# RobotCtrl_Func.net
KiCad netlist of a schematic drawn in Altium Designer
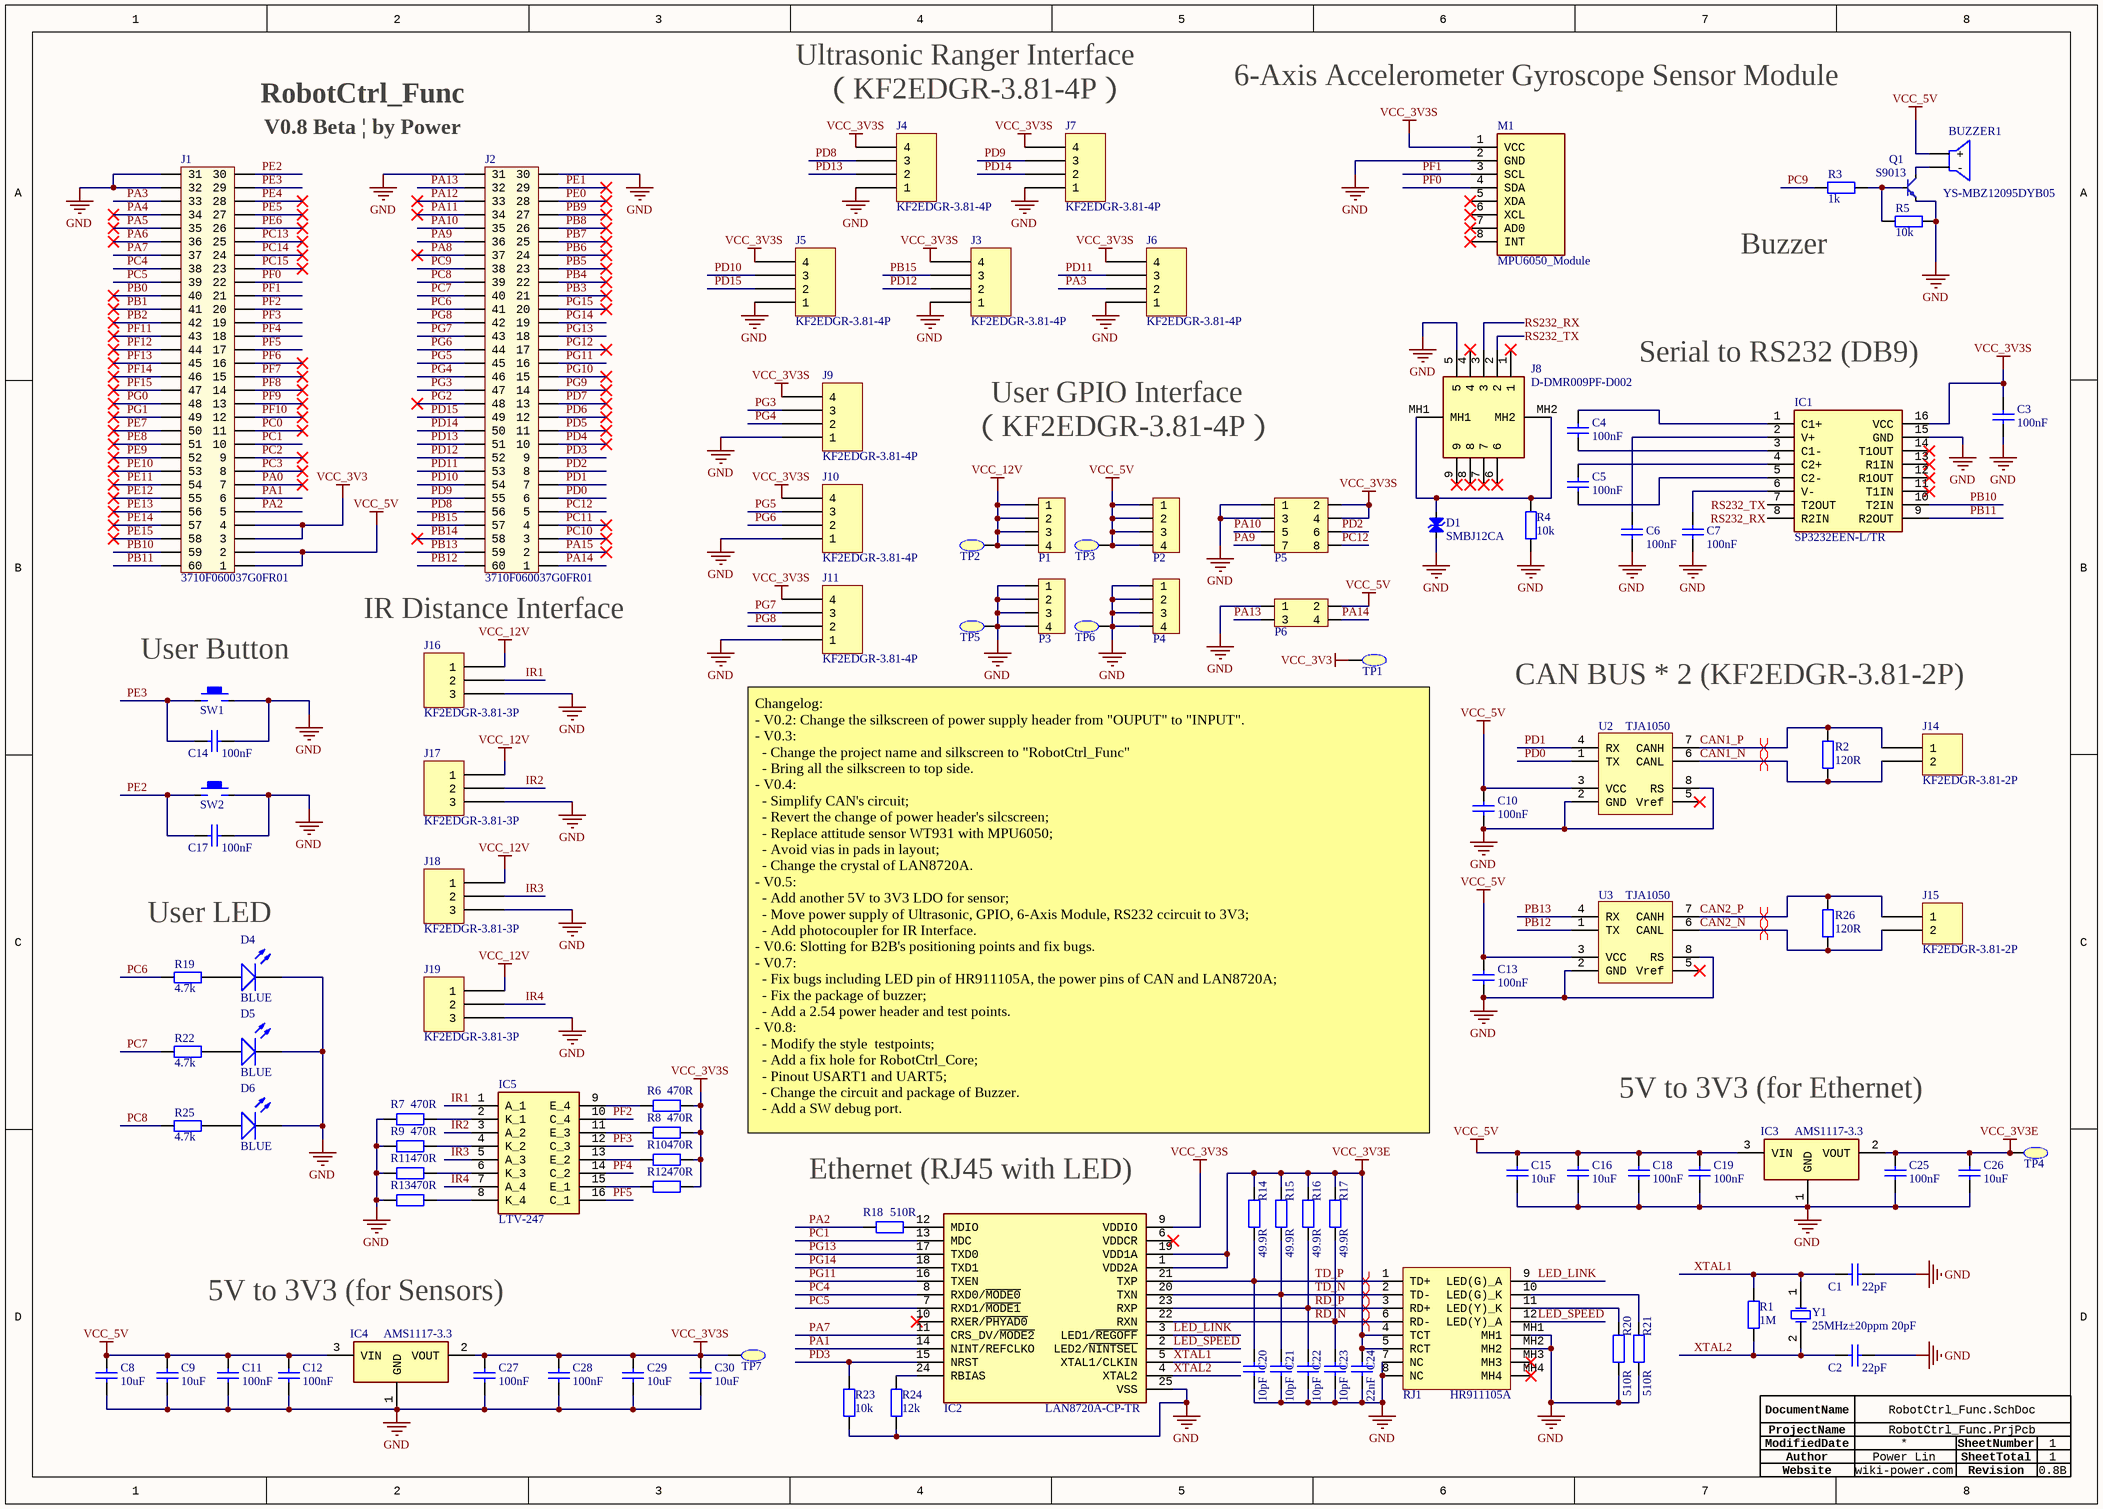
[diagram p0: RobotCtrl_Func.SchDoc]

(export (version "E")
  (design (tool "Eeschema 10.0.6"))
  (components
    (comp (ref "BUZZER1")
      (value "YS-MBZ12095DYB05")
      (footprint "DIP,P=7.6mm")
      (description "YS-MBZ12095DYB05 有源蜂鸣器")
      (libsource (lib "Power_Lib_Altium") (part "BUZZER"))
    )
    (comp (ref "C1")
      (value "22pF")
      (footprint "CAP-0603")
      (description "贴片电容")
      (libsource (lib "Power_Lib_Altium") (part "CAP"))
    )
    (comp (ref "C2")
      (value "22pF")
      (footprint "CAP-0603")
      (description "贴片电容")
      (libsource (lib "Power_Lib_Altium") (part "CAP"))
    )
    (comp (ref "C3")
      (value "100nF")
      (footprint "CAP-0603")
      (description "贴片电容")
      (libsource (lib "Power_Lib_Altium") (part "CAP"))
    )
    (comp (ref "C4")
      (value "100nF")
      (footprint "CAP-0603")
      (description "贴片电容")
      (libsource (lib "Power_Lib_Altium") (part "CAP"))
    )
    (comp (ref "C5")
      (value "100nF")
      (footprint "CAP-0603")
      (description "贴片电容")
      (libsource (lib "Power_Lib_Altium") (part "CAP"))
    )
    (comp (ref "C6")
      (value "100nF")
      (footprint "CAP-0603")
      (description "贴片电容")
      (libsource (lib "Power_Lib_Altium") (part "CAP"))
    )
    (comp (ref "C7")
      (value "100nF")
      (footprint "CAP-0603")
      (description "贴片电容")
      (libsource (lib "Power_Lib_Altium") (part "CAP"))
    )
    (comp (ref "C8")
      (value "10uF")
      (footprint "CAP-0603")
      (description "贴片电容")
      (libsource (lib "Power_Lib_Altium") (part "CAP"))
    )
    (comp (ref "C9")
      (value "10uF")
      (footprint "CAP-0603")
      (description "贴片电容")
      (libsource (lib "Power_Lib_Altium") (part "CAP"))
    )
    (comp (ref "C10")
      (value "100nF")
      (footprint "CAP-0603")
      (description "贴片电容")
      (libsource (lib "Power_Lib_Altium") (part "CAP"))
    )
    (comp (ref "C11")
      (value "100nF")
      (footprint "CAP-0603")
      (description "贴片电容")
      (libsource (lib "Power_Lib_Altium") (part "CAP"))
    )
    (comp (ref "C12")
      (value "100nF")
      (footprint "CAP-0603")
      (description "贴片电容")
      (libsource (lib "Power_Lib_Altium") (part "CAP"))
    )
    (comp (ref "C13")
      (value "100nF")
      (footprint "CAP-0603")
      (description "贴片电容")
      (libsource (lib "Power_Lib_Altium") (part "CAP"))
    )
    (comp (ref "C14")
      (value "100nF")
      (footprint "CAP-0603")
      (description "贴片电容")
      (libsource (lib "Power_Lib_Altium") (part "CAP"))
    )
    (comp (ref "C15")
      (value "10uF")
      (footprint "CAP-0603")
      (description "贴片电容")
      (libsource (lib "Power_Lib_Altium") (part "CAP"))
    )
    (comp (ref "C16")
      (value "10uF")
      (footprint "CAP-0603")
      (description "贴片电容")
      (libsource (lib "Power_Lib_Altium") (part "CAP"))
    )
    (comp (ref "C17")
      (value "100nF")
      (footprint "CAP-0603")
      (description "贴片电容")
      (libsource (lib "Power_Lib_Altium") (part "CAP"))
    )
    (comp (ref "C18")
      (value "100nF")
      (footprint "CAP-0603")
      (description "贴片电容")
      (libsource (lib "Power_Lib_Altium") (part "CAP"))
    )
    (comp (ref "C19")
      (value "100nF")
      (footprint "CAP-0603")
      (description "贴片电容")
      (libsource (lib "Power_Lib_Altium") (part "CAP"))
    )
    (comp (ref "C20")
      (value "10pF")
      (footprint "CAP-0603")
      (description "贴片电容")
      (libsource (lib "Power_Lib_Altium") (part "CAP"))
    )
    (comp (ref "C21")
      (value "10pF")
      (footprint "CAP-0603")
      (description "贴片电容")
      (libsource (lib "Power_Lib_Altium") (part "CAP"))
    )
    (comp (ref "C22")
      (value "10pF")
      (footprint "CAP-0603")
      (description "贴片电容")
      (libsource (lib "Power_Lib_Altium") (part "CAP"))
    )
    (comp (ref "C23")
      (value "10pF")
      (footprint "CAP-0603")
      (description "贴片电容")
      (libsource (lib "Power_Lib_Altium") (part "CAP"))
    )
    (comp (ref "C24")
      (value "22nF")
      (footprint "CAP-0603")
      (description "贴片电容")
      (libsource (lib "Power_Lib_Altium") (part "CAP"))
    )
    (comp (ref "C25")
      (value "100nF")
      (footprint "CAP-0603")
      (description "贴片电容")
      (libsource (lib "Power_Lib_Altium") (part "CAP"))
    )
    (comp (ref "C26")
      (value "10uF")
      (footprint "CAP-0603")
      (description "贴片电容")
      (libsource (lib "Power_Lib_Altium") (part "CAP"))
    )
    (comp (ref "C27")
      (value "100nF")
      (footprint "CAP-0603")
      (description "贴片电容")
      (libsource (lib "Power_Lib_Altium") (part "CAP"))
    )
    (comp (ref "C28")
      (value "100nF")
      (footprint "CAP-0603")
      (description "贴片电容")
      (libsource (lib "Power_Lib_Altium") (part "CAP"))
    )
    (comp (ref "C29")
      (value "10uF")
      (footprint "CAP-0603")
      (description "贴片电容")
      (libsource (lib "Power_Lib_Altium") (part "CAP"))
    )
    (comp (ref "C30")
      (value "10uF")
      (footprint "CAP-0603")
      (description "贴片电容")
      (libsource (lib "Power_Lib_Altium") (part "CAP"))
    )
    (comp (ref "D1")
      (value "SMBJ12CA")
      (footprint "DO-214AA/SMB")
      (libsource (lib "Power_Lib_Altium") (part "TVS_C"))
    )
    (comp (ref "D4")
      (value "BLUE")
      (footprint "LED-0603")
      (description "发光二极管")
      (libsource (lib "Power_Lib_Altium") (part "LED"))
    )
    (comp (ref "D5")
      (value "BLUE")
      (footprint "LED-0603")
      (description "发光二极管")
      (libsource (lib "Power_Lib_Altium") (part "LED"))
    )
    (comp (ref "D6")
      (value "BLUE")
      (footprint "LED-0603")
      (description "发光二极管")
      (libsource (lib "Power_Lib_Altium") (part "LED"))
    )
    (comp (ref "IC1")
      (value "SP3232EEN-L/TR")
      (footprint "SOIC-16_150mil")
      (description "RS232 芯片")
      (fields (field (name "MOUSER PART NUMBER") "701-SP3232EEN-L/TR"))
      (libsource (lib "Power_Lib_Altium") (part "SP3232EEN"))
    )
    (comp (ref "IC2")
      (value "LAN8720A-CP-TR")
      (footprint "QFN-24-4x4")
      (description "Integrated Circuit")
      (fields (field (name "MOUSER PART NUMBER") "886-LAN8720A-CP-TR"))
      (libsource (lib "Power_Lib_Altium") (part "LAN8720A-CP-TR"))
    )
    (comp (ref "IC3")
      (value "AMS1117-3.3")
      (footprint "SOT-223")
      (description "AMS1117-3.3 1.0A")
      (fields (field (name "MANUFACTURER_PART_NUMBER") "SI2302DS") (field (name "RS PART NUMBER") "7983053P"))
      (libsource (lib "Power_Lib_Altium") (part "AMS1117"))
    )
    (comp (ref "IC4")
      (value "AMS1117-3.3")
      (footprint "SOT-223")
      (description "AMS1117-3.3 1.0A")
      (fields (field (name "MANUFACTURER_PART_NUMBER") "SI2302DS") (field (name "RS PART NUMBER") "7983053P"))
      (libsource (lib "Power_Lib_Altium") (part "AMS1117"))
    )
    (comp (ref "IC5")
      (value "LTV-247")
      (footprint "Power_Lib_Altium:LTV247")
      (description "Integrated Circuit")
      (fields (field (name "MOUSER PART NUMBER") "859-LTV-247"))
      (libsource (lib "Power_Lib_Altium") (part "LTV-247"))
    )
    (comp (ref "J1")
      (value "3710F060037G0FR01")
      (footprint "3710M060037G3FT01")
      (description "B2B Connector")
      (libsource (lib "Power_Lib_Altium") (part "3710M/F"))
    )
    (comp (ref "J2")
      (value "3710F060037G0FR01")
      (footprint "3710M060037G3FT01")
      (description "B2B Connector")
      (libsource (lib "Power_Lib_Altium") (part "3710M/F"))
    )
    (comp (ref "J3")
      (value "KF2EDGR-3.81-4P")
      (footprint "FCI 06-381-4PIN")
      (description "TERM BLOCK HDR 4POS 90DEG 3.81MM")
      (fields (field (name "PART NUMBER") "OQ0432510000G") (field (name "MANUFACTURER") "Amphenol Anytek"))
      (libsource (lib "Power_Lib_Altium") (part "KF2EDGR-3.81-4P"))
    )
    (comp (ref "J4")
      (value "KF2EDGR-3.81-4P")
      (footprint "FCI 06-381-4PIN")
      (description "TERM BLOCK HDR 4POS 90DEG 3.81MM")
      (fields (field (name "PART NUMBER") "OQ0432510000G") (field (name "MANUFACTURER") "Amphenol Anytek"))
      (libsource (lib "Power_Lib_Altium") (part "KF2EDGR-3.81-4P"))
    )
    (comp (ref "J5")
      (value "KF2EDGR-3.81-4P")
      (footprint "FCI 06-381-4PIN")
      (description "TERM BLOCK HDR 4POS 90DEG 3.81MM")
      (fields (field (name "PART NUMBER") "OQ0432510000G") (field (name "MANUFACTURER") "Amphenol Anytek"))
      (libsource (lib "Power_Lib_Altium") (part "KF2EDGR-3.81-4P"))
    )
    (comp (ref "J6")
      (value "KF2EDGR-3.81-4P")
      (footprint "FCI 06-381-4PIN")
      (description "TERM BLOCK HDR 4POS 90DEG 3.81MM")
      (fields (field (name "PART NUMBER") "OQ0432510000G") (field (name "MANUFACTURER") "Amphenol Anytek"))
      (libsource (lib "Power_Lib_Altium") (part "KF2EDGR-3.81-4P"))
    )
    (comp (ref "J7")
      (value "KF2EDGR-3.81-4P")
      (footprint "FCI 06-381-4PIN")
      (description "TERM BLOCK HDR 4POS 90DEG 3.81MM")
      (fields (field (name "PART NUMBER") "OQ0432510000G") (field (name "MANUFACTURER") "Amphenol Anytek"))
      (libsource (lib "Power_Lib_Altium") (part "KF2EDGR-3.81-4P"))
    )
    (comp (ref "J8")
      (value "D-DMR009PF-D002")
      (footprint "Through Hole,P=2.77mm")
      (description "D-Sub 连接器")
      (fields
        (field (name "MANUFACTURER_PART_NUMBER") "5747844-5")
        (field (name "MOUSER PART NUMBER") "571-5747844-5")
      )
      (libsource (lib "Power_Lib_Altium") (part "DB9"))
    )
    (comp (ref "J9")
      (value "KF2EDGR-3.81-4P")
      (footprint "FCI 06-381-4PIN")
      (description "TERM BLOCK HDR 4POS 90DEG 3.81MM")
      (fields (field (name "PART NUMBER") "OQ0432510000G") (field (name "MANUFACTURER") "Amphenol Anytek"))
      (libsource (lib "Power_Lib_Altium") (part "KF2EDGR-3.81-4P"))
    )
    (comp (ref "J10")
      (value "KF2EDGR-3.81-4P")
      (footprint "FCI 06-381-4PIN")
      (description "TERM BLOCK HDR 4POS 90DEG 3.81MM")
      (fields (field (name "PART NUMBER") "OQ0432510000G") (field (name "MANUFACTURER") "Amphenol Anytek"))
      (libsource (lib "Power_Lib_Altium") (part "KF2EDGR-3.81-4P"))
    )
    (comp (ref "J11")
      (value "KF2EDGR-3.81-4P")
      (footprint "FCI 06-381-4PIN")
      (description "TERM BLOCK HDR 4POS 90DEG 3.81MM")
      (fields (field (name "PART NUMBER") "OQ0432510000G") (field (name "MANUFACTURER") "Amphenol Anytek"))
      (libsource (lib "Power_Lib_Altium") (part "KF2EDGR-3.81-4P"))
    )
    (comp (ref "J14")
      (value "KF2EDGR-3.81-2P")
      (footprint "FCI 06-381-2PIN")
      (description "TERM BLOCK HDR 2POS 90DEG 3.81MM")
      (fields (field (name "PART NUMBER") "OQ0232510000G") (field (name "MANUFACTURER") "Amphenol Anytek"))
      (libsource (lib "Power_Lib_Altium") (part "KF2EDGR-3.81-2P"))
    )
    (comp (ref "J15")
      (value "KF2EDGR-3.81-2P")
      (footprint "FCI 06-381-2PIN")
      (description "TERM BLOCK HDR 2POS 90DEG 3.81MM")
      (fields (field (name "PART NUMBER") "OQ0232510000G") (field (name "MANUFACTURER") "Amphenol Anytek"))
      (libsource (lib "Power_Lib_Altium") (part "KF2EDGR-3.81-2P"))
    )
    (comp (ref "J16")
      (value "KF2EDGR-3.81-3P")
      (footprint "FCI 06-381-3PIN")
      (description "TERM BLOCK HDR 3POS 90DEG 3.81MM")
      (fields (field (name "MANUFACTURER") "Amphenol Anytek") (field (name "PART NUMBER") "OQ0332510000G"))
      (libsource (lib "Power_Lib_Altium") (part "KF2EDGR-3.81-3P"))
    )
    (comp (ref "J17")
      (value "KF2EDGR-3.81-3P")
      (footprint "FCI 06-381-3PIN")
      (description "TERM BLOCK HDR 3POS 90DEG 3.81MM")
      (fields (field (name "MANUFACTURER") "Amphenol Anytek") (field (name "PART NUMBER") "OQ0332510000G"))
      (libsource (lib "Power_Lib_Altium") (part "KF2EDGR-3.81-3P"))
    )
    (comp (ref "J18")
      (value "KF2EDGR-3.81-3P")
      (footprint "FCI 06-381-3PIN")
      (description "TERM BLOCK HDR 3POS 90DEG 3.81MM")
      (fields (field (name "MANUFACTURER") "Amphenol Anytek") (field (name "PART NUMBER") "OQ0332510000G"))
      (libsource (lib "Power_Lib_Altium") (part "KF2EDGR-3.81-3P"))
    )
    (comp (ref "J19")
      (value "KF2EDGR-3.81-3P")
      (footprint "FCI 06-381-3PIN")
      (description "TERM BLOCK HDR 3POS 90DEG 3.81MM")
      (fields (field (name "MANUFACTURER") "Amphenol Anytek") (field (name "PART NUMBER") "OQ0332510000G"))
      (libsource (lib "Power_Lib_Altium") (part "KF2EDGR-3.81-3P"))
    )
    (comp (ref "M1")
      (value "MPU6050_Module")
      (footprint "MPU6050_Module_SMD")
      (description "MPU6050 陀螺仪")
      (libsource (lib "Power_Lib_Altium") (part "MPU6050_Module"))
    )
    (comp (ref "P1")
      (value "HDR1x4_2.54")
      (footprint "HDR1X4_2.54")
      (description "Header")
      (libsource (lib "Power_Lib_Altium") (part "HDR1x4_2.54"))
    )
    (comp (ref "P2")
      (value "HDR1x4_2.54")
      (footprint "HDR1X4_2.54")
      (description "Header")
      (libsource (lib "Power_Lib_Altium") (part "HDR1x4_2.54"))
    )
    (comp (ref "P3")
      (value "HDR1x4_2.54")
      (footprint "HDR1X4_2.54")
      (description "Header")
      (libsource (lib "Power_Lib_Altium") (part "HDR1x4_2.54"))
    )
    (comp (ref "P4")
      (value "HDR1x4_2.54")
      (footprint "HDR1X4_2.54")
      (description "Header")
      (libsource (lib "Power_Lib_Altium") (part "HDR1x4_2.54"))
    )
    (comp (ref "P5")
      (value "HDR2x4_2.54")
      (footprint "HDR2X4_2.54_180")
      (description "Header")
      (libsource (lib "Power_Lib_Altium") (part "HDR2x4_2.54"))
    )
    (comp (ref "P6")
      (value "HDR2x2_2.54")
      (footprint "HDR2X2_2.54_180")
      (description "Header")
      (libsource (lib "Power_Lib_Altium") (part "HDR2x2_2.54"))
    )
    (comp (ref "Q1")
      (value "S9013")
      (footprint "SOT-23-3")
      (libsource (lib "Power_Lib_Altium") (part "BJT_NPN"))
    )
    (comp (ref "R1")
      (value "1M")
      (footprint "R-0603")
      (description "贴片电阻")
      (libsource (lib "") (part "RES_1"))
    )
    (comp (ref "R2")
      (value "120R")
      (footprint "R-0603")
      (description "贴片电阻")
      (libsource (lib "Power_Lib_Altium") (part "RES"))
    )
    (comp (ref "R3")
      (value "1k")
      (footprint "R-0603")
      (description "贴片电阻")
      (libsource (lib "") (part "RES_3"))
    )
    (comp (ref "R4")
      (value "10k")
      (footprint "R-0603")
      (description "贴片电阻")
      (libsource (lib "") (part "RES_1"))
    )
    (comp (ref "R5")
      (value "10k")
      (footprint "R-0603")
      (description "贴片电阻")
      (libsource (lib "") (part "RES_2"))
    )
    (comp (ref "R6")
      (value "470R")
      (footprint "R-0603")
      (description "216R~540R, higer is better")
      (libsource (lib "") (part "RES_2"))
    )
    (comp (ref "R7")
      (value "470R")
      (footprint "R-0603")
      (description "216R~540R, higer is better")
      (libsource (lib "") (part "RES_2"))
    )
    (comp (ref "R8")
      (value "470R")
      (footprint "R-0603")
      (description "216R~540R, higer is better")
      (libsource (lib "") (part "RES_2"))
    )
    (comp (ref "R9")
      (value "470R")
      (footprint "R-0603")
      (description "216R~540R, higer is better")
      (libsource (lib "") (part "RES_2"))
    )
    (comp (ref "R10")
      (value "470R")
      (footprint "R-0603")
      (description "216R~540R, higer is better")
      (libsource (lib "") (part "RES_2"))
    )
    (comp (ref "R11")
      (value "470R")
      (footprint "R-0603")
      (description "216R~540R, higer is better")
      (libsource (lib "") (part "RES_2"))
    )
    (comp (ref "R12")
      (value "470R")
      (footprint "R-0603")
      (description "216R~540R, higer is better")
      (libsource (lib "") (part "RES_2"))
    )
    (comp (ref "R13")
      (value "470R")
      (footprint "R-0603")
      (description "216R~540R, higer is better")
      (libsource (lib "") (part "RES_2"))
    )
    (comp (ref "R14")
      (value "49.9R")
      (footprint "R-0603")
      (description "贴片电阻")
      (libsource (lib "") (part "RES_1"))
    )
    (comp (ref "R15")
      (value "49.9R")
      (footprint "R-0603")
      (description "贴片电阻")
      (libsource (lib "") (part "RES_1"))
    )
    (comp (ref "R16")
      (value "49.9R")
      (footprint "R-0603")
      (description "贴片电阻")
      (libsource (lib "") (part "RES_1"))
    )
    (comp (ref "R17")
      (value "49.9R")
      (footprint "R-0603")
      (description "贴片电阻")
      (libsource (lib "") (part "RES_1"))
    )
    (comp (ref "R18")
      (value "510R")
      (footprint "R-0603")
      (description "贴片电阻")
      (libsource (lib "") (part "RES_2"))
    )
    (comp (ref "R19")
      (value "4.7k")
      (footprint "R-0603")
      (description "贴片电阻")
      (libsource (lib "") (part "RES_2"))
    )
    (comp (ref "R20")
      (value "510R")
      (footprint "R-0603")
      (description "贴片电阻")
      (libsource (lib "") (part "RES_1"))
    )
    (comp (ref "R21")
      (value "510R")
      (footprint "R-0603")
      (description "贴片电阻")
      (libsource (lib "") (part "RES_1"))
    )
    (comp (ref "R22")
      (value "4.7k")
      (footprint "R-0603")
      (description "贴片电阻")
      (libsource (lib "") (part "RES_2"))
    )
    (comp (ref "R23")
      (value "10k")
      (footprint "R-0603")
      (description "贴片电阻")
      (libsource (lib "Power_Lib_Altium") (part "RES"))
    )
    (comp (ref "R24")
      (value "12k")
      (footprint "R-0603")
      (description "贴片电阻")
      (libsource (lib "Power_Lib_Altium") (part "RES"))
    )
    (comp (ref "R25")
      (value "4.7k")
      (footprint "R-0603")
      (description "贴片电阻")
      (libsource (lib "") (part "RES_2"))
    )
    (comp (ref "R26")
      (value "120R")
      (footprint "R-0603")
      (description "贴片电阻")
      (libsource (lib "Power_Lib_Altium") (part "RES"))
    )
    (comp (ref "RJ1")
      (value "HR911105A")
      (footprint "HR911105A")
      (description "内置变压器的RJ45")
      (libsource (lib "Power_Lib_Altium") (part "RJ45_LED"))
    )
    (comp (ref "SW1")
      (value "KEY")
      (footprint "KEY-4P-4.2*3.4*2.5")
      (description "按键开关")
      (libsource (lib "Power_Lib_Altium") (part "KEY"))
    )
    (comp (ref "SW2")
      (value "KEY")
      (footprint "KEY-4P-4.2*3.4*2.5")
      (description "按键开关")
      (libsource (lib "Power_Lib_Altium") (part "KEY"))
    )
    (comp (ref "TP1")
      (value "TestPoint")
      (footprint "TestPoint")
      (description "测试点")
      (libsource (lib "Power_Lib_Altium") (part "TestPoint"))
    )
    (comp (ref "TP2")
      (value "TestPoint")
      (footprint "TestPoint")
      (description "测试点")
      (libsource (lib "Power_Lib_Altium") (part "TestPoint"))
    )
    (comp (ref "TP3")
      (value "TestPoint")
      (footprint "TestPoint")
      (description "测试点")
      (libsource (lib "Power_Lib_Altium") (part "TestPoint"))
    )
    (comp (ref "TP4")
      (value "TestPoint")
      (footprint "TestPoint")
      (description "测试点")
      (libsource (lib "Power_Lib_Altium") (part "TestPoint"))
    )
    (comp (ref "TP5")
      (value "TestPoint")
      (footprint "TestPoint")
      (description "测试点")
      (libsource (lib "Power_Lib_Altium") (part "TestPoint"))
    )
    (comp (ref "TP6")
      (value "TestPoint")
      (footprint "TestPoint")
      (description "测试点")
      (libsource (lib "Power_Lib_Altium") (part "TestPoint"))
    )
    (comp (ref "TP7")
      (value "TestPoint")
      (footprint "TestPoint")
      (description "测试点")
      (libsource (lib "Power_Lib_Altium") (part "TestPoint"))
    )
    (comp (ref "U2")
      (value "TJA1050")
      (footprint "SOIC_8")
      (description "CAN 控制器（5V）")
      (libsource (lib "Power_Lib_Altium") (part "TJA1050"))
    )
    (comp (ref "U3")
      (value "TJA1050")
      (footprint "SOIC_8")
      (description "CAN 控制器（5V）")
      (libsource (lib "Power_Lib_Altium") (part "TJA1050"))
    )
    (comp (ref "Y1")
      (value "25MHz±20ppm 20pF")
      (footprint "SMD5032-2P")
      (description "TAXM25M2QLFCDT1T")
      (libsource (lib "Power_Lib_Altium") (part "Crystal"))
    )
  )
  (nets
    (net (code "1") (name "/CAN1_N") (class "Default")
      (node (ref "J14") (pin "2") (pinfunction "2_2") (pintype "passive"))
      (node (ref "R2") (pin "2") (pinfunction "2_2") (pintype "passive"))
      (node (ref "U2") (pin "6") (pinfunction "CANL_6") (pintype "passive"))
    )
    (net (code "2") (name "/CAN1_P") (class "Default")
      (node (ref "J14") (pin "1") (pinfunction "1_1") (pintype "passive"))
      (node (ref "R2") (pin "1") (pinfunction "1_1") (pintype "passive"))
      (node (ref "U2") (pin "7") (pinfunction "CANH_7") (pintype "passive"))
    )
    (net (code "3") (name "/CAN2_N") (class "Default")
      (node (ref "J15") (pin "2") (pinfunction "2_2") (pintype "passive"))
      (node (ref "R26") (pin "2") (pinfunction "2_2") (pintype "passive"))
      (node (ref "U3") (pin "6") (pinfunction "CANL_6") (pintype "passive"))
    )
    (net (code "4") (name "/CAN2_P") (class "Default")
      (node (ref "J15") (pin "1") (pinfunction "1_1") (pintype "passive"))
      (node (ref "R26") (pin "1") (pinfunction "1_1") (pintype "passive"))
      (node (ref "U3") (pin "7") (pinfunction "CANH_7") (pintype "passive"))
    )
    (net (code "5") (name "/IR1") (class "Default")
      (node (ref "IC5") (pin "1") (pinfunction "A_1_1") (pintype "passive"))
      (node (ref "J16") (pin "2") (pinfunction "2_2") (pintype "passive"))
    )
    (net (code "6") (name "/IR2") (class "Default")
      (node (ref "IC5") (pin "3") (pinfunction "A_2_3") (pintype "passive"))
      (node (ref "J17") (pin "2") (pinfunction "2_2") (pintype "passive"))
    )
    (net (code "7") (name "/IR3") (class "Default")
      (node (ref "IC5") (pin "5") (pinfunction "A_3_5") (pintype "passive"))
      (node (ref "J18") (pin "2") (pinfunction "2_2") (pintype "passive"))
    )
    (net (code "8") (name "/IR4") (class "Default")
      (node (ref "IC5") (pin "7") (pinfunction "A_4_7") (pintype "passive"))
      (node (ref "J19") (pin "2") (pinfunction "2_2") (pintype "passive"))
    )
    (net (code "9") (name "/LED_LINK") (class "Default")
      (node (ref "IC2") (pin "3") (pinfunction "LED1/~{REGOFF}_3") (pintype "passive"))
      (node (ref "RJ1") (pin "9") (pinfunction "LED(G)_A_9") (pintype "passive"))
    )
    (net (code "10") (name "/LED_SPEED") (class "Default")
      (node (ref "IC2") (pin "2") (pinfunction "LED2/~{NINTSEL}_2") (pintype "passive"))
      (node (ref "RJ1") (pin "12") (pinfunction "LED(Y)_A_12") (pintype "passive"))
    )
    (net (code "11") (name "/PA0") (class "Default")
      (node (ref "J1") (pin "7") (pinfunction "7_7") (pintype "passive+no_connect"))
    )
    (net (code "12") (name "/PA1") (class "Default")
      (node (ref "IC2") (pin "14") (pinfunction "NINT/REFCLKO_14") (pintype "passive"))
      (node (ref "J1") (pin "6") (pinfunction "6_6") (pintype "passive"))
    )
    (net (code "13") (name "/PA2") (class "Default")
      (node (ref "J1") (pin "5") (pinfunction "5_5") (pintype "passive"))
      (node (ref "R18") (pin "2") (pinfunction "2_2") (pintype "passive"))
    )
    (net (code "14") (name "/PA3") (class "Default")
      (node (ref "J1") (pin "33") (pinfunction "33_33") (pintype "passive"))
      (node (ref "J6") (pin "2") (pinfunction "2_2") (pintype "passive"))
    )
    (net (code "15") (name "/PA4") (class "Default")
      (node (ref "J1") (pin "34") (pinfunction "34_34") (pintype "passive+no_connect"))
    )
    (net (code "16") (name "/PA5") (class "Default")
      (node (ref "J1") (pin "35") (pinfunction "35_35") (pintype "passive+no_connect"))
    )
    (net (code "17") (name "/PA6") (class "Default")
      (node (ref "J1") (pin "36") (pinfunction "36_36") (pintype "passive+no_connect"))
    )
    (net (code "18") (name "/PA7") (class "Default")
      (node (ref "IC2") (pin "11") (pinfunction "CRS_DV/~{MODE2}_11") (pintype "passive"))
      (node (ref "J1") (pin "37") (pinfunction "37_37") (pintype "passive"))
    )
    (net (code "19") (name "/PA8") (class "Default")
      (node (ref "J2") (pin "37") (pinfunction "37_37") (pintype "passive+no_connect"))
    )
    (net (code "20") (name "/PA9") (class "Default")
      (node (ref "J2") (pin "36") (pinfunction "36_36") (pintype "passive"))
      (node (ref "P5") (pin "7") (pinfunction "7_7") (pintype "passive"))
    )
    (net (code "21") (name "/PA10") (class "Default")
      (node (ref "J2") (pin "35") (pinfunction "35_35") (pintype "passive"))
      (node (ref "P5") (pin "5") (pinfunction "5_5") (pintype "passive"))
    )
    (net (code "22") (name "/PA11") (class "Default")
      (node (ref "J2") (pin "34") (pinfunction "34_34") (pintype "passive+no_connect"))
    )
    (net (code "23") (name "/PA12") (class "Default")
      (node (ref "J2") (pin "33") (pinfunction "33_33") (pintype "passive+no_connect"))
    )
    (net (code "24") (name "/PA13") (class "Default")
      (node (ref "J2") (pin "32") (pinfunction "32_32") (pintype "passive"))
      (node (ref "P6") (pin "3") (pinfunction "3_3") (pintype "passive"))
    )
    (net (code "25") (name "/PA14") (class "Default")
      (node (ref "J2") (pin "1") (pinfunction "1_1") (pintype "passive"))
      (node (ref "P6") (pin "4") (pinfunction "4_4") (pintype "passive"))
    )
    (net (code "26") (name "/PA15") (class "Default")
      (node (ref "J2") (pin "2") (pinfunction "2_2") (pintype "passive+no_connect"))
    )
    (net (code "27") (name "/PB0") (class "Default")
      (node (ref "J1") (pin "40") (pinfunction "40_40") (pintype "passive+no_connect"))
    )
    (net (code "28") (name "/PB1") (class "Default")
      (node (ref "J1") (pin "41") (pinfunction "41_41") (pintype "passive+no_connect"))
    )
    (net (code "29") (name "/PB2") (class "Default")
      (node (ref "J1") (pin "42") (pinfunction "42_42") (pintype "passive+no_connect"))
    )
    (net (code "30") (name "/PB3") (class "Default")
      (node (ref "J2") (pin "21") (pinfunction "21_21") (pintype "passive+no_connect"))
    )
    (net (code "31") (name "/PB4") (class "Default")
      (node (ref "J2") (pin "22") (pinfunction "22_22") (pintype "passive+no_connect"))
    )
    (net (code "32") (name "/PB5") (class "Default")
      (node (ref "J2") (pin "23") (pinfunction "23_23") (pintype "passive+no_connect"))
    )
    (net (code "33") (name "/PB6") (class "Default")
      (node (ref "J2") (pin "24") (pinfunction "24_24") (pintype "passive+no_connect"))
    )
    (net (code "34") (name "/PB7") (class "Default")
      (node (ref "J2") (pin "25") (pinfunction "25_25") (pintype "passive+no_connect"))
    )
    (net (code "35") (name "/PB8") (class "Default")
      (node (ref "J2") (pin "26") (pinfunction "26_26") (pintype "passive+no_connect"))
    )
    (net (code "36") (name "/PB9") (class "Default")
      (node (ref "J2") (pin "27") (pinfunction "27_27") (pintype "passive+no_connect"))
    )
    (net (code "37") (name "/PB10") (class "Default")
      (node (ref "IC1") (pin "10") (pinfunction "T2IN_10") (pintype "passive"))
      (node (ref "J1") (pin "59") (pinfunction "59_59") (pintype "passive"))
    )
    (net (code "38") (name "/PB11") (class "Default")
      (node (ref "IC1") (pin "9") (pinfunction "R2OUT_9") (pintype "passive"))
      (node (ref "J1") (pin "60") (pinfunction "60_60") (pintype "passive"))
    )
    (net (code "39") (name "/PB12") (class "Default")
      (node (ref "J2") (pin "60") (pinfunction "60_60") (pintype "passive"))
      (node (ref "U3") (pin "1") (pinfunction "TX_1") (pintype "passive"))
    )
    (net (code "40") (name "/PB13") (class "Default")
      (node (ref "J2") (pin "59") (pinfunction "59_59") (pintype "passive"))
      (node (ref "U3") (pin "4") (pinfunction "RX_4") (pintype "passive"))
    )
    (net (code "41") (name "/PB14") (class "Default")
      (node (ref "J2") (pin "58") (pinfunction "58_58") (pintype "passive+no_connect"))
    )
    (net (code "42") (name "/PB15") (class "Default")
      (node (ref "J2") (pin "57") (pinfunction "57_57") (pintype "passive"))
      (node (ref "J3") (pin "3") (pinfunction "3_3") (pintype "passive"))
    )
    (net (code "43") (name "/PC0") (class "Default")
      (node (ref "J1") (pin "11") (pinfunction "11_11") (pintype "passive+no_connect"))
    )
    (net (code "44") (name "/PC1") (class "Default")
      (node (ref "IC2") (pin "13") (pinfunction "MDC_13") (pintype "passive"))
      (node (ref "J1") (pin "10") (pinfunction "10_10") (pintype "passive"))
    )
    (net (code "45") (name "/PC2") (class "Default")
      (node (ref "J1") (pin "9") (pinfunction "9_9") (pintype "passive+no_connect"))
    )
    (net (code "46") (name "/PC3") (class "Default")
      (node (ref "J1") (pin "8") (pinfunction "8_8") (pintype "passive+no_connect"))
    )
    (net (code "47") (name "/PC4") (class "Default")
      (node (ref "IC2") (pin "8") (pinfunction "RXD0/~{MODE0}_8") (pintype "passive"))
      (node (ref "J1") (pin "38") (pinfunction "38_38") (pintype "passive"))
    )
    (net (code "48") (name "/PC5") (class "Default")
      (node (ref "IC2") (pin "7") (pinfunction "RXD1/~{MODE1}_7") (pintype "passive"))
      (node (ref "J1") (pin "39") (pinfunction "39_39") (pintype "passive"))
    )
    (net (code "49") (name "/PC6") (class "Default")
      (node (ref "J2") (pin "41") (pinfunction "41_41") (pintype "passive"))
      (node (ref "R19") (pin "2") (pinfunction "2_2") (pintype "passive"))
    )
    (net (code "50") (name "/PC7") (class "Default")
      (node (ref "J2") (pin "40") (pinfunction "40_40") (pintype "passive"))
      (node (ref "R22") (pin "2") (pinfunction "2_2") (pintype "passive"))
    )
    (net (code "51") (name "/PC8") (class "Default")
      (node (ref "J2") (pin "39") (pinfunction "39_39") (pintype "passive"))
      (node (ref "R25") (pin "2") (pinfunction "2_2") (pintype "passive"))
    )
    (net (code "52") (name "/PC9") (class "Default")
      (node (ref "J2") (pin "38") (pinfunction "38_38") (pintype "passive"))
      (node (ref "R3") (pin "1") (pinfunction "1_1") (pintype "passive"))
    )
    (net (code "53") (name "/PC10") (class "Default")
      (node (ref "J2") (pin "3") (pinfunction "3_3") (pintype "passive+no_connect"))
    )
    (net (code "54") (name "/PC11") (class "Default")
      (node (ref "J2") (pin "4") (pinfunction "4_4") (pintype "passive+no_connect"))
    )
    (net (code "55") (name "/PC12") (class "Default")
      (node (ref "J2") (pin "5") (pinfunction "5_5") (pintype "passive"))
      (node (ref "P5") (pin "8") (pinfunction "8_8") (pintype "passive"))
    )
    (net (code "56") (name "/PC13") (class "Default")
      (node (ref "J1") (pin "25") (pinfunction "25_25") (pintype "passive+no_connect"))
    )
    (net (code "57") (name "/PC14") (class "Default")
      (node (ref "J1") (pin "24") (pinfunction "24_24") (pintype "passive+no_connect"))
    )
    (net (code "58") (name "/PC15") (class "Default")
      (node (ref "J1") (pin "23") (pinfunction "23_23") (pintype "passive+no_connect"))
    )
    (net (code "59") (name "/PD0") (class "Default")
      (node (ref "J2") (pin "6") (pinfunction "6_6") (pintype "passive"))
      (node (ref "U2") (pin "1") (pinfunction "TX_1") (pintype "passive"))
    )
    (net (code "60") (name "/PD1") (class "Default")
      (node (ref "J2") (pin "7") (pinfunction "7_7") (pintype "passive"))
      (node (ref "U2") (pin "4") (pinfunction "RX_4") (pintype "passive"))
    )
    (net (code "61") (name "/PD2") (class "Default")
      (node (ref "J2") (pin "8") (pinfunction "8_8") (pintype "passive"))
      (node (ref "P5") (pin "6") (pinfunction "6_6") (pintype "passive"))
    )
    (net (code "62") (name "/PD3") (class "Default")
      (node (ref "IC2") (pin "15") (pinfunction "NRST_15") (pintype "passive"))
      (node (ref "J2") (pin "9") (pinfunction "9_9") (pintype "passive"))
      (node (ref "R23") (pin "1") (pinfunction "1_1") (pintype "passive"))
    )
    (net (code "63") (name "/PD4") (class "Default")
      (node (ref "J2") (pin "10") (pinfunction "10_10") (pintype "passive+no_connect"))
    )
    (net (code "64") (name "/PD5") (class "Default")
      (node (ref "J2") (pin "11") (pinfunction "11_11") (pintype "passive+no_connect"))
    )
    (net (code "65") (name "/PD6") (class "Default")
      (node (ref "J2") (pin "12") (pinfunction "12_12") (pintype "passive+no_connect"))
    )
    (net (code "66") (name "/PD7") (class "Default")
      (node (ref "J2") (pin "13") (pinfunction "13_13") (pintype "passive+no_connect"))
    )
    (net (code "67") (name "/PD8") (class "Default")
      (node (ref "J2") (pin "56") (pinfunction "56_56") (pintype "passive"))
      (node (ref "J4") (pin "3") (pinfunction "3_3") (pintype "passive"))
    )
    (net (code "68") (name "/PD9") (class "Default")
      (node (ref "J2") (pin "55") (pinfunction "55_55") (pintype "passive"))
      (node (ref "J7") (pin "3") (pinfunction "3_3") (pintype "passive"))
    )
    (net (code "69") (name "/PD10") (class "Default")
      (node (ref "J2") (pin "54") (pinfunction "54_54") (pintype "passive"))
      (node (ref "J5") (pin "3") (pinfunction "3_3") (pintype "passive"))
    )
    (net (code "70") (name "/PD11") (class "Default")
      (node (ref "J2") (pin "53") (pinfunction "53_53") (pintype "passive"))
      (node (ref "J6") (pin "3") (pinfunction "3_3") (pintype "passive"))
    )
    (net (code "71") (name "/PD12") (class "Default")
      (node (ref "J2") (pin "52") (pinfunction "52_52") (pintype "passive"))
      (node (ref "J3") (pin "2") (pinfunction "2_2") (pintype "passive"))
    )
    (net (code "72") (name "/PD13") (class "Default")
      (node (ref "J2") (pin "51") (pinfunction "51_51") (pintype "passive"))
      (node (ref "J4") (pin "2") (pinfunction "2_2") (pintype "passive"))
    )
    (net (code "73") (name "/PD14") (class "Default")
      (node (ref "J2") (pin "50") (pinfunction "50_50") (pintype "passive"))
      (node (ref "J7") (pin "2") (pinfunction "2_2") (pintype "passive"))
    )
    (net (code "74") (name "/PD15") (class "Default")
      (node (ref "J2") (pin "49") (pinfunction "49_49") (pintype "passive"))
      (node (ref "J5") (pin "2") (pinfunction "2_2") (pintype "passive"))
    )
    (net (code "75") (name "/PE0") (class "Default")
      (node (ref "J2") (pin "28") (pinfunction "28_28") (pintype "passive+no_connect"))
    )
    (net (code "76") (name "/PE1") (class "Default")
      (node (ref "J2") (pin "29") (pinfunction "29_29") (pintype "passive+no_connect"))
    )
    (net (code "77") (name "/PE2") (class "Default")
      (node (ref "C17") (pin "2") (pinfunction "2_2") (pintype "passive"))
      (node (ref "J1") (pin "30") (pinfunction "30_30") (pintype "passive"))
      (node (ref "SW2") (pin "1") (pinfunction "1_1") (pintype "passive"))
    )
    (net (code "78") (name "/PE3") (class "Default")
      (node (ref "C14") (pin "2") (pinfunction "2_2") (pintype "passive"))
      (node (ref "J1") (pin "29") (pinfunction "29_29") (pintype "passive"))
      (node (ref "SW1") (pin "1") (pinfunction "1_1") (pintype "passive"))
    )
    (net (code "79") (name "/PE4") (class "Default")
      (node (ref "J1") (pin "28") (pinfunction "28_28") (pintype "passive+no_connect"))
    )
    (net (code "80") (name "/PE5") (class "Default")
      (node (ref "J1") (pin "27") (pinfunction "27_27") (pintype "passive+no_connect"))
    )
    (net (code "81") (name "/PE6") (class "Default")
      (node (ref "J1") (pin "26") (pinfunction "26_26") (pintype "passive+no_connect"))
    )
    (net (code "82") (name "/PE7") (class "Default")
      (node (ref "J1") (pin "50") (pinfunction "50_50") (pintype "passive+no_connect"))
    )
    (net (code "83") (name "/PE8") (class "Default")
      (node (ref "J1") (pin "51") (pinfunction "51_51") (pintype "passive+no_connect"))
    )
    (net (code "84") (name "/PE9") (class "Default")
      (node (ref "J1") (pin "52") (pinfunction "52_52") (pintype "passive+no_connect"))
    )
    (net (code "85") (name "/PE10") (class "Default")
      (node (ref "J1") (pin "53") (pinfunction "53_53") (pintype "passive+no_connect"))
    )
    (net (code "86") (name "/PE11") (class "Default")
      (node (ref "J1") (pin "54") (pinfunction "54_54") (pintype "passive+no_connect"))
    )
    (net (code "87") (name "/PE12") (class "Default")
      (node (ref "J1") (pin "55") (pinfunction "55_55") (pintype "passive+no_connect"))
    )
    (net (code "88") (name "/PE13") (class "Default")
      (node (ref "J1") (pin "56") (pinfunction "56_56") (pintype "passive+no_connect"))
    )
    (net (code "89") (name "/PE14") (class "Default")
      (node (ref "J1") (pin "57") (pinfunction "57_57") (pintype "passive+no_connect"))
    )
    (net (code "90") (name "/PE15") (class "Default")
      (node (ref "J1") (pin "58") (pinfunction "58_58") (pintype "passive+no_connect"))
    )
    (net (code "91") (name "/PF0") (class "Default")
      (node (ref "J1") (pin "22") (pinfunction "22_22") (pintype "passive"))
      (node (ref "M1") (pin "4") (pinfunction "SDA_4") (pintype "passive"))
    )
    (net (code "92") (name "/PF1") (class "Default")
      (node (ref "J1") (pin "21") (pinfunction "21_21") (pintype "passive"))
      (node (ref "M1") (pin "3") (pinfunction "SCL_3") (pintype "passive"))
    )
    (net (code "93") (name "/PF2") (class "Default")
      (node (ref "IC5") (pin "10") (pinfunction "C_4_10") (pintype "passive"))
      (node (ref "J1") (pin "20") (pinfunction "20_20") (pintype "passive"))
    )
    (net (code "94") (name "/PF3") (class "Default")
      (node (ref "IC5") (pin "12") (pinfunction "C_3_12") (pintype "passive"))
      (node (ref "J1") (pin "19") (pinfunction "19_19") (pintype "passive"))
    )
    (net (code "95") (name "/PF4") (class "Default")
      (node (ref "IC5") (pin "14") (pinfunction "C_2_14") (pintype "passive"))
      (node (ref "J1") (pin "18") (pinfunction "18_18") (pintype "passive"))
    )
    (net (code "96") (name "/PF5") (class "Default")
      (node (ref "IC5") (pin "16") (pinfunction "C_1_16") (pintype "passive"))
      (node (ref "J1") (pin "17") (pinfunction "17_17") (pintype "passive"))
    )
    (net (code "97") (name "/PF6") (class "Default")
      (node (ref "J1") (pin "16") (pinfunction "16_16") (pintype "passive+no_connect"))
    )
    (net (code "98") (name "/PF7") (class "Default")
      (node (ref "J1") (pin "15") (pinfunction "15_15") (pintype "passive+no_connect"))
    )
    (net (code "99") (name "/PF8") (class "Default")
      (node (ref "J1") (pin "14") (pinfunction "14_14") (pintype "passive+no_connect"))
    )
    (net (code "100") (name "/PF9") (class "Default")
      (node (ref "J1") (pin "13") (pinfunction "13_13") (pintype "passive+no_connect"))
    )
    (net (code "101") (name "/PF10") (class "Default")
      (node (ref "J1") (pin "12") (pinfunction "12_12") (pintype "passive+no_connect"))
    )
    (net (code "102") (name "/PF11") (class "Default")
      (node (ref "J1") (pin "43") (pinfunction "43_43") (pintype "passive+no_connect"))
    )
    (net (code "103") (name "/PF12") (class "Default")
      (node (ref "J1") (pin "44") (pinfunction "44_44") (pintype "passive+no_connect"))
    )
    (net (code "104") (name "/PF13") (class "Default")
      (node (ref "J1") (pin "45") (pinfunction "45_45") (pintype "passive+no_connect"))
    )
    (net (code "105") (name "/PF14") (class "Default")
      (node (ref "J1") (pin "46") (pinfunction "46_46") (pintype "passive+no_connect"))
    )
    (net (code "106") (name "/PF15") (class "Default")
      (node (ref "J1") (pin "47") (pinfunction "47_47") (pintype "passive+no_connect"))
    )
    (net (code "107") (name "/PG0") (class "Default")
      (node (ref "J1") (pin "48") (pinfunction "48_48") (pintype "passive+no_connect"))
    )
    (net (code "108") (name "/PG1") (class "Default")
      (node (ref "J1") (pin "49") (pinfunction "49_49") (pintype "passive+no_connect"))
    )
    (net (code "109") (name "/PG2") (class "Default")
      (node (ref "J2") (pin "48") (pinfunction "48_48") (pintype "passive+no_connect"))
    )
    (net (code "110") (name "/PG3") (class "Default")
      (node (ref "J2") (pin "47") (pinfunction "47_47") (pintype "passive"))
      (node (ref "J9") (pin "3") (pinfunction "3_3") (pintype "passive"))
    )
    (net (code "111") (name "/PG4") (class "Default")
      (node (ref "J2") (pin "46") (pinfunction "46_46") (pintype "passive"))
      (node (ref "J9") (pin "2") (pinfunction "2_2") (pintype "passive"))
    )
    (net (code "112") (name "/PG5") (class "Default")
      (node (ref "J10") (pin "3") (pinfunction "3_3") (pintype "passive"))
      (node (ref "J2") (pin "45") (pinfunction "45_45") (pintype "passive"))
    )
    (net (code "113") (name "/PG6") (class "Default")
      (node (ref "J10") (pin "2") (pinfunction "2_2") (pintype "passive"))
      (node (ref "J2") (pin "44") (pinfunction "44_44") (pintype "passive"))
    )
    (net (code "114") (name "/PG7") (class "Default")
      (node (ref "J11") (pin "3") (pinfunction "3_3") (pintype "passive"))
      (node (ref "J2") (pin "43") (pinfunction "43_43") (pintype "passive"))
    )
    (net (code "115") (name "/PG8") (class "Default")
      (node (ref "J11") (pin "2") (pinfunction "2_2") (pintype "passive"))
      (node (ref "J2") (pin "42") (pinfunction "42_42") (pintype "passive"))
    )
    (net (code "116") (name "/PG9") (class "Default")
      (node (ref "J2") (pin "14") (pinfunction "14_14") (pintype "passive+no_connect"))
    )
    (net (code "117") (name "/PG10") (class "Default")
      (node (ref "J2") (pin "15") (pinfunction "15_15") (pintype "passive+no_connect"))
    )
    (net (code "118") (name "/PG11") (class "Default")
      (node (ref "IC2") (pin "16") (pinfunction "TXEN_16") (pintype "passive"))
      (node (ref "J2") (pin "16") (pinfunction "16_16") (pintype "passive"))
    )
    (net (code "119") (name "/PG12") (class "Default")
      (node (ref "J2") (pin "17") (pinfunction "17_17") (pintype "passive+no_connect"))
    )
    (net (code "120") (name "/PG13") (class "Default")
      (node (ref "IC2") (pin "17") (pinfunction "TXD0_17") (pintype "passive"))
      (node (ref "J2") (pin "18") (pinfunction "18_18") (pintype "passive"))
    )
    (net (code "121") (name "/PG14") (class "Default")
      (node (ref "IC2") (pin "18") (pinfunction "TXD1_18") (pintype "passive"))
      (node (ref "J2") (pin "19") (pinfunction "19_19") (pintype "passive"))
    )
    (net (code "122") (name "/PG15") (class "Default")
      (node (ref "J2") (pin "20") (pinfunction "20_20") (pintype "passive+no_connect"))
    )
    (net (code "123") (name "/RD_N") (class "Default")
      (node (ref "C23") (pin "2") (pinfunction "2_2") (pintype "passive"))
      (node (ref "IC2") (pin "22") (pinfunction "RXN_22") (pintype "passive"))
      (node (ref "R17") (pin "1") (pinfunction "1_1") (pintype "passive"))
      (node (ref "RJ1") (pin "6") (pinfunction "RD-_6") (pintype "passive"))
    )
    (net (code "124") (name "/RD_P") (class "Default")
      (node (ref "C22") (pin "2") (pinfunction "2_2") (pintype "passive"))
      (node (ref "IC2") (pin "23") (pinfunction "RXP_23") (pintype "passive"))
      (node (ref "R16") (pin "1") (pinfunction "1_1") (pintype "passive"))
      (node (ref "RJ1") (pin "3") (pinfunction "RD+_3") (pintype "passive"))
    )
    (net (code "125") (name "/RS232_RX") (class "Default")
      (node (ref "IC1") (pin "8") (pinfunction "R2IN_8") (pintype "passive"))
      (node (ref "J8") (pin "3") (pinfunction "3_3") (pintype "passive"))
    )
    (net (code "126") (name "/RS232_TX") (class "Default")
      (node (ref "IC1") (pin "7") (pinfunction "T2OUT_7") (pintype "passive"))
      (node (ref "J8") (pin "2") (pinfunction "2_2") (pintype "passive"))
    )
    (net (code "127") (name "/TD_N") (class "Default")
      (node (ref "C21") (pin "2") (pinfunction "2_2") (pintype "passive"))
      (node (ref "IC2") (pin "20") (pinfunction "TXN_20") (pintype "passive"))
      (node (ref "R15") (pin "1") (pinfunction "1_1") (pintype "passive"))
      (node (ref "RJ1") (pin "2") (pinfunction "TD-_2") (pintype "passive"))
    )
    (net (code "128") (name "/TD_P") (class "Default")
      (node (ref "C20") (pin "2") (pinfunction "2_2") (pintype "passive"))
      (node (ref "IC2") (pin "21") (pinfunction "TXP_21") (pintype "passive"))
      (node (ref "R14") (pin "1") (pinfunction "1_1") (pintype "passive"))
      (node (ref "RJ1") (pin "1") (pinfunction "TD+_1") (pintype "passive"))
    )
    (net (code "129") (name "/XTAL1") (class "Default")
      (node (ref "C1") (pin "2") (pinfunction "2_2") (pintype "passive"))
      (node (ref "IC2") (pin "5") (pinfunction "XTAL1/CLKIN_5") (pintype "passive"))
      (node (ref "R1") (pin "2") (pinfunction "2_2") (pintype "passive"))
      (node (ref "Y1") (pin "1") (pinfunction "OSC1_1") (pintype "passive"))
    )
    (net (code "130") (name "/XTAL2") (class "Default")
      (node (ref "C2") (pin "2") (pinfunction "2_2") (pintype "passive"))
      (node (ref "IC2") (pin "4") (pinfunction "XTAL2_4") (pintype "passive"))
      (node (ref "R1") (pin "1") (pinfunction "1_1") (pintype "passive"))
      (node (ref "Y1") (pin "2") (pinfunction "OSC2_2") (pintype "passive"))
    )
    (net (code "131") (name "GND") (class "Default")
      (node (ref "C1") (pin "1") (pinfunction "1_1") (pintype "passive"))
      (node (ref "C10") (pin "1") (pinfunction "1_1") (pintype "passive"))
      (node (ref "C11") (pin "1") (pinfunction "1_1") (pintype "passive"))
      (node (ref "C12") (pin "1") (pinfunction "1_1") (pintype "passive"))
      (node (ref "C13") (pin "1") (pinfunction "1_1") (pintype "passive"))
      (node (ref "C14") (pin "1") (pinfunction "1_1") (pintype "passive"))
      (node (ref "C15") (pin "1") (pinfunction "1_1") (pintype "passive"))
      (node (ref "C16") (pin "1") (pinfunction "1_1") (pintype "passive"))
      (node (ref "C17") (pin "1") (pinfunction "1_1") (pintype "passive"))
      (node (ref "C18") (pin "1") (pinfunction "1_1") (pintype "passive"))
      (node (ref "C19") (pin "1") (pinfunction "1_1") (pintype "passive"))
      (node (ref "C2") (pin "1") (pinfunction "1_1") (pintype "passive"))
      (node (ref "C20") (pin "1") (pinfunction "1_1") (pintype "passive"))
      (node (ref "C21") (pin "1") (pinfunction "1_1") (pintype "passive"))
      (node (ref "C22") (pin "1") (pinfunction "1_1") (pintype "passive"))
      (node (ref "C23") (pin "1") (pinfunction "1_1") (pintype "passive"))
      (node (ref "C24") (pin "1") (pinfunction "1_1") (pintype "passive"))
      (node (ref "C25") (pin "1") (pinfunction "1_1") (pintype "passive"))
      (node (ref "C26") (pin "1") (pinfunction "1_1") (pintype "passive"))
      (node (ref "C27") (pin "1") (pinfunction "1_1") (pintype "passive"))
      (node (ref "C28") (pin "1") (pinfunction "1_1") (pintype "passive"))
      (node (ref "C29") (pin "1") (pinfunction "1_1") (pintype "passive"))
      (node (ref "C3") (pin "1") (pinfunction "1_1") (pintype "passive"))
      (node (ref "C30") (pin "1") (pinfunction "1_1") (pintype "passive"))
      (node (ref "C6") (pin "1") (pinfunction "1_1") (pintype "passive"))
      (node (ref "C7") (pin "1") (pinfunction "1_1") (pintype "passive"))
      (node (ref "C8") (pin "1") (pinfunction "1_1") (pintype "passive"))
      (node (ref "C9") (pin "1") (pinfunction "1_1") (pintype "passive"))
      (node (ref "D1") (pin "1") (pinfunction "1_1") (pintype "passive"))
      (node (ref "D4") (pin "K") (pinfunction "K_K") (pintype "passive"))
      (node (ref "D5") (pin "K") (pinfunction "K_K") (pintype "passive"))
      (node (ref "D6") (pin "K") (pinfunction "K_K") (pintype "passive"))
      (node (ref "IC1") (pin "15") (pinfunction "GND_15") (pintype "passive"))
      (node (ref "IC2") (pin "25") (pinfunction "VSS_25") (pintype "passive"))
      (node (ref "IC3") (pin "1") (pinfunction "GND_1") (pintype "passive"))
      (node (ref "IC4") (pin "1") (pinfunction "GND_1") (pintype "passive"))
      (node (ref "J1") (pin "31") (pinfunction "31_31") (pintype "passive"))
      (node (ref "J1") (pin "32") (pinfunction "32_32") (pintype "passive"))
      (node (ref "J10") (pin "1") (pinfunction "1_1") (pintype "passive"))
      (node (ref "J11") (pin "1") (pinfunction "1_1") (pintype "passive"))
      (node (ref "J16") (pin "3") (pinfunction "3_3") (pintype "passive"))
      (node (ref "J17") (pin "3") (pinfunction "3_3") (pintype "passive"))
      (node (ref "J18") (pin "3") (pinfunction "3_3") (pintype "passive"))
      (node (ref "J19") (pin "3") (pinfunction "3_3") (pintype "passive"))
      (node (ref "J2") (pin "30") (pinfunction "30_30") (pintype "passive"))
      (node (ref "J2") (pin "31") (pinfunction "31_31") (pintype "passive"))
      (node (ref "J3") (pin "1") (pinfunction "1_1") (pintype "passive"))
      (node (ref "J4") (pin "1") (pinfunction "1_1") (pintype "passive"))
      (node (ref "J5") (pin "1") (pinfunction "1_1") (pintype "passive"))
      (node (ref "J6") (pin "1") (pinfunction "1_1") (pintype "passive"))
      (node (ref "J7") (pin "1") (pinfunction "1_1") (pintype "passive"))
      (node (ref "J8") (pin "5") (pinfunction "5_5") (pintype "passive"))
      (node (ref "J9") (pin "1") (pinfunction "1_1") (pintype "passive"))
      (node (ref "M1") (pin "2") (pinfunction "GND_2") (pintype "passive"))
      (node (ref "P3") (pin "1") (pinfunction "1_1") (pintype "passive"))
      (node (ref "P3") (pin "2") (pinfunction "2_2") (pintype "passive"))
      (node (ref "P3") (pin "3") (pinfunction "3_3") (pintype "passive"))
      (node (ref "P3") (pin "4") (pinfunction "4_4") (pintype "passive"))
      (node (ref "P4") (pin "1") (pinfunction "1_1") (pintype "passive"))
      (node (ref "P4") (pin "2") (pinfunction "2_2") (pintype "passive"))
      (node (ref "P4") (pin "3") (pinfunction "3_3") (pintype "passive"))
      (node (ref "P4") (pin "4") (pinfunction "4_4") (pintype "passive"))
      (node (ref "P5") (pin "1") (pinfunction "1_1") (pintype "passive"))
      (node (ref "P5") (pin "3") (pinfunction "3_3") (pintype "passive"))
      (node (ref "P6") (pin "1") (pinfunction "1_1") (pintype "passive"))
      (node (ref "Q1") (pin "2") (pinfunction "E_2") (pintype "passive"))
      (node (ref "R11") (pin "2") (pinfunction "2_2") (pintype "passive"))
      (node (ref "R13") (pin "2") (pinfunction "2_2") (pintype "passive"))
      (node (ref "R20") (pin "1") (pinfunction "1_1") (pintype "passive"))
      (node (ref "R21") (pin "1") (pinfunction "1_1") (pintype "passive"))
      (node (ref "R23") (pin "2") (pinfunction "2_2") (pintype "passive"))
      (node (ref "R24") (pin "2") (pinfunction "2_2") (pintype "passive"))
      (node (ref "R4") (pin "1") (pinfunction "1_1") (pintype "passive"))
      (node (ref "R5") (pin "1") (pinfunction "1_1") (pintype "passive"))
      (node (ref "R7") (pin "2") (pinfunction "2_2") (pintype "passive"))
      (node (ref "R9") (pin "2") (pinfunction "2_2") (pintype "passive"))
      (node (ref "RJ1") (pin "7") (pinfunction "NC_7") (pintype "passive"))
      (node (ref "RJ1") (pin "8") (pinfunction "NC_8") (pintype "passive"))
      (node (ref "RJ1") (pin "MH1") (pinfunction "MH1_MH1") (pintype "passive"))
      (node (ref "RJ1") (pin "MH2") (pinfunction "MH2_MH2") (pintype "passive"))
      (node (ref "SW1") (pin "2") (pinfunction "2_2") (pintype "passive"))
      (node (ref "SW2") (pin "2") (pinfunction "2_2") (pintype "passive"))
      (node (ref "TP5") (pin "1") (pinfunction "1_1") (pintype "passive"))
      (node (ref "TP6") (pin "1") (pinfunction "1_1") (pintype "passive"))
      (node (ref "U2") (pin "2") (pinfunction "GND_2") (pintype "passive"))
      (node (ref "U2") (pin "8") (pinfunction "RS_8") (pintype "passive"))
      (node (ref "U3") (pin "2") (pinfunction "GND_2") (pintype "passive"))
      (node (ref "U3") (pin "8") (pinfunction "RS_8") (pintype "passive"))
    )
    (net (code "132") (name "Net-(BUZZER1--)") (class "Default")
      (node (ref "BUZZER1") (pin "2") (pinfunction "-_2") (pintype "passive"))
      (node (ref "Q1") (pin "3") (pinfunction "C_3") (pintype "passive"))
    )
    (net (code "133") (name "Net-(D1-Pad2)") (class "Default")
      (node (ref "D1") (pin "2") (pinfunction "2_2") (pintype "passive"))
      (node (ref "J8") (pin "MH1") (pinfunction "MH1_MH1") (pintype "passive"))
      (node (ref "J8") (pin "MH2") (pinfunction "MH2_MH2") (pintype "passive"))
      (node (ref "R4") (pin "2") (pinfunction "2_2") (pintype "passive"))
    )
    (net (code "134") (name "Net-(D4-PadA)") (class "Default")
      (node (ref "D4") (pin "A") (pinfunction "A_A") (pintype "passive"))
      (node (ref "R19") (pin "1") (pinfunction "1_1") (pintype "passive"))
    )
    (net (code "135") (name "Net-(D5-PadA)") (class "Default")
      (node (ref "D5") (pin "A") (pinfunction "A_A") (pintype "passive"))
      (node (ref "R22") (pin "1") (pinfunction "1_1") (pintype "passive"))
    )
    (net (code "136") (name "Net-(D6-PadA)") (class "Default")
      (node (ref "D6") (pin "A") (pinfunction "A_A") (pintype "passive"))
      (node (ref "R25") (pin "1") (pinfunction "1_1") (pintype "passive"))
    )
    (net (code "137") (name "Net-(IC1-C1+)") (class "Default")
      (node (ref "C4") (pin "2") (pinfunction "2_2") (pintype "passive"))
      (node (ref "IC1") (pin "1") (pinfunction "C1+_1") (pintype "passive"))
    )
    (net (code "138") (name "Net-(IC1-C1-)") (class "Default")
      (node (ref "C4") (pin "1") (pinfunction "1_1") (pintype "passive"))
      (node (ref "IC1") (pin "3") (pinfunction "C1-_3") (pintype "passive"))
    )
    (net (code "139") (name "Net-(IC1-C2+)") (class "Default")
      (node (ref "C5") (pin "2") (pinfunction "2_2") (pintype "passive"))
      (node (ref "IC1") (pin "4") (pinfunction "C2+_4") (pintype "passive"))
    )
    (net (code "140") (name "Net-(IC1-C2-)") (class "Default")
      (node (ref "C5") (pin "1") (pinfunction "1_1") (pintype "passive"))
      (node (ref "IC1") (pin "5") (pinfunction "C2-_5") (pintype "passive"))
    )
    (net (code "141") (name "Net-(IC1-V+)") (class "Default")
      (node (ref "C6") (pin "2") (pinfunction "2_2") (pintype "passive"))
      (node (ref "IC1") (pin "2") (pinfunction "V+_2") (pintype "passive"))
    )
    (net (code "142") (name "Net-(IC1-V-)") (class "Default")
      (node (ref "C7") (pin "2") (pinfunction "2_2") (pintype "passive"))
      (node (ref "IC1") (pin "6") (pinfunction "V-_6") (pintype "passive"))
    )
    (net (code "143") (name "Net-(IC2-MDIO)") (class "Default")
      (node (ref "IC2") (pin "12") (pinfunction "MDIO_12") (pintype "passive"))
      (node (ref "R18") (pin "1") (pinfunction "1_1") (pintype "passive"))
    )
    (net (code "144") (name "Net-(IC2-RBIAS)") (class "Default")
      (node (ref "IC2") (pin "24") (pinfunction "RBIAS_24") (pintype "passive"))
      (node (ref "R24") (pin "1") (pinfunction "1_1") (pintype "passive"))
    )
    (net (code "145") (name "Net-(IC5-E_1)") (class "Default")
      (node (ref "IC5") (pin "15") (pinfunction "E_1_15") (pintype "passive"))
      (node (ref "R12") (pin "2") (pinfunction "2_2") (pintype "passive"))
    )
    (net (code "146") (name "Net-(IC5-E_2)") (class "Default")
      (node (ref "IC5") (pin "13") (pinfunction "E_2_13") (pintype "passive"))
      (node (ref "R10") (pin "2") (pinfunction "2_2") (pintype "passive"))
    )
    (net (code "147") (name "Net-(IC5-E_3)") (class "Default")
      (node (ref "IC5") (pin "11") (pinfunction "E_3_11") (pintype "passive"))
      (node (ref "R8") (pin "2") (pinfunction "2_2") (pintype "passive"))
    )
    (net (code "148") (name "Net-(IC5-E_4)") (class "Default")
      (node (ref "IC5") (pin "9") (pinfunction "E_4_9") (pintype "passive"))
      (node (ref "R6") (pin "2") (pinfunction "2_2") (pintype "passive"))
    )
    (net (code "149") (name "Net-(IC5-K_1)") (class "Default")
      (node (ref "IC5") (pin "2") (pinfunction "K_1_2") (pintype "passive"))
      (node (ref "R7") (pin "1") (pinfunction "1_1") (pintype "passive"))
    )
    (net (code "150") (name "Net-(IC5-K_2)") (class "Default")
      (node (ref "IC5") (pin "4") (pinfunction "K_2_4") (pintype "passive"))
      (node (ref "R9") (pin "1") (pinfunction "1_1") (pintype "passive"))
    )
    (net (code "151") (name "Net-(IC5-K_3)") (class "Default")
      (node (ref "IC5") (pin "6") (pinfunction "K_3_6") (pintype "passive"))
      (node (ref "R11") (pin "1") (pinfunction "1_1") (pintype "passive"))
    )
    (net (code "152") (name "Net-(IC5-K_4)") (class "Default")
      (node (ref "IC5") (pin "8") (pinfunction "K_4_8") (pintype "passive"))
      (node (ref "R13") (pin "1") (pinfunction "1_1") (pintype "passive"))
    )
    (net (code "153") (name "Net-(Q1-B)") (class "Default")
      (node (ref "Q1") (pin "1") (pinfunction "B_1") (pintype "passive"))
      (node (ref "R3") (pin "2") (pinfunction "2_2") (pintype "passive"))
      (node (ref "R5") (pin "2") (pinfunction "2_2") (pintype "passive"))
    )
    (net (code "154") (name "Net-(RJ1-LED(G)_K)") (class "Default")
      (node (ref "R21") (pin "2") (pinfunction "2_2") (pintype "passive"))
      (node (ref "RJ1") (pin "10") (pinfunction "LED(G)_K_10") (pintype "passive"))
    )
    (net (code "155") (name "Net-(RJ1-LED(Y)_K)") (class "Default")
      (node (ref "R20") (pin "2") (pinfunction "2_2") (pintype "passive"))
      (node (ref "RJ1") (pin "11") (pinfunction "LED(Y)_K_11") (pintype "passive"))
    )
    (net (code "156") (name "VCC_3V3") (class "Default")
      (node (ref "J1") (pin "3") (pinfunction "3_3") (pintype "passive"))
      (node (ref "J1") (pin "4") (pinfunction "4_4") (pintype "passive"))
      (node (ref "TP1") (pin "1") (pinfunction "1_1") (pintype "passive"))
    )
    (net (code "157") (name "VCC_3V3E") (class "Default")
      (node (ref "C24") (pin "2") (pinfunction "2_2") (pintype "passive"))
      (node (ref "C25") (pin "2") (pinfunction "2_2") (pintype "passive"))
      (node (ref "C26") (pin "2") (pinfunction "2_2") (pintype "passive"))
      (node (ref "IC2") (pin "1") (pinfunction "VDD2A_1") (pintype "passive"))
      (node (ref "IC2") (pin "19") (pinfunction "VDD1A_19") (pintype "passive"))
      (node (ref "IC3") (pin "2") (pinfunction "VOUT_2") (pintype "passive"))
      (node (ref "R14") (pin "2") (pinfunction "2_2") (pintype "passive"))
      (node (ref "R15") (pin "2") (pinfunction "2_2") (pintype "passive"))
      (node (ref "R16") (pin "2") (pinfunction "2_2") (pintype "passive"))
      (node (ref "R17") (pin "2") (pinfunction "2_2") (pintype "passive"))
      (node (ref "RJ1") (pin "4") (pinfunction "TCT_4") (pintype "passive"))
      (node (ref "RJ1") (pin "5") (pinfunction "RCT_5") (pintype "passive"))
      (node (ref "TP4") (pin "1") (pinfunction "1_1") (pintype "passive"))
    )
    (net (code "158") (name "VCC_3V3S") (class "Default")
      (node (ref "C27") (pin "2") (pinfunction "2_2") (pintype "passive"))
      (node (ref "C28") (pin "2") (pinfunction "2_2") (pintype "passive"))
      (node (ref "C29") (pin "2") (pinfunction "2_2") (pintype "passive"))
      (node (ref "C3") (pin "2") (pinfunction "2_2") (pintype "passive"))
      (node (ref "C30") (pin "2") (pinfunction "2_2") (pintype "passive"))
      (node (ref "IC1") (pin "16") (pinfunction "VCC_16") (pintype "passive"))
      (node (ref "IC2") (pin "9") (pinfunction "VDDIO_9") (pintype "passive"))
      (node (ref "IC4") (pin "2") (pinfunction "VOUT_2") (pintype "passive"))
      (node (ref "J10") (pin "4") (pinfunction "4_4") (pintype "passive"))
      (node (ref "J11") (pin "4") (pinfunction "4_4") (pintype "passive"))
      (node (ref "J3") (pin "4") (pinfunction "4_4") (pintype "passive"))
      (node (ref "J4") (pin "4") (pinfunction "4_4") (pintype "passive"))
      (node (ref "J5") (pin "4") (pinfunction "4_4") (pintype "passive"))
      (node (ref "J6") (pin "4") (pinfunction "4_4") (pintype "passive"))
      (node (ref "J7") (pin "4") (pinfunction "4_4") (pintype "passive"))
      (node (ref "J9") (pin "4") (pinfunction "4_4") (pintype "passive"))
      (node (ref "M1") (pin "1") (pinfunction "VCC_1") (pintype "passive"))
      (node (ref "P5") (pin "2") (pinfunction "2_2") (pintype "passive"))
      (node (ref "P5") (pin "4") (pinfunction "4_4") (pintype "passive"))
      (node (ref "R10") (pin "1") (pinfunction "1_1") (pintype "passive"))
      (node (ref "R12") (pin "1") (pinfunction "1_1") (pintype "passive"))
      (node (ref "R6") (pin "1") (pinfunction "1_1") (pintype "passive"))
      (node (ref "R8") (pin "1") (pinfunction "1_1") (pintype "passive"))
      (node (ref "TP7") (pin "1") (pinfunction "1_1") (pintype "passive"))
    )
    (net (code "159") (name "VCC_5V") (class "Default")
      (node (ref "BUZZER1") (pin "1") (pinfunction "+_1") (pintype "passive"))
      (node (ref "C10") (pin "2") (pinfunction "2_2") (pintype "passive"))
      (node (ref "C11") (pin "2") (pinfunction "2_2") (pintype "passive"))
      (node (ref "C12") (pin "2") (pinfunction "2_2") (pintype "passive"))
      (node (ref "C13") (pin "2") (pinfunction "2_2") (pintype "passive"))
      (node (ref "C15") (pin "2") (pinfunction "2_2") (pintype "passive"))
      (node (ref "C16") (pin "2") (pinfunction "2_2") (pintype "passive"))
      (node (ref "C18") (pin "2") (pinfunction "2_2") (pintype "passive"))
      (node (ref "C19") (pin "2") (pinfunction "2_2") (pintype "passive"))
      (node (ref "C8") (pin "2") (pinfunction "2_2") (pintype "passive"))
      (node (ref "C9") (pin "2") (pinfunction "2_2") (pintype "passive"))
      (node (ref "IC3") (pin "3") (pinfunction "VIN_3") (pintype "passive"))
      (node (ref "IC4") (pin "3") (pinfunction "VIN_3") (pintype "passive"))
      (node (ref "J1") (pin "1") (pinfunction "1_1") (pintype "passive"))
      (node (ref "J1") (pin "2") (pinfunction "2_2") (pintype "passive"))
      (node (ref "P2") (pin "1") (pinfunction "1_1") (pintype "passive"))
      (node (ref "P2") (pin "2") (pinfunction "2_2") (pintype "passive"))
      (node (ref "P2") (pin "3") (pinfunction "3_3") (pintype "passive"))
      (node (ref "P2") (pin "4") (pinfunction "4_4") (pintype "passive"))
      (node (ref "P6") (pin "2") (pinfunction "2_2") (pintype "passive"))
      (node (ref "TP3") (pin "1") (pinfunction "1_1") (pintype "passive"))
      (node (ref "U2") (pin "3") (pinfunction "VCC_3") (pintype "passive"))
      (node (ref "U3") (pin "3") (pinfunction "VCC_3") (pintype "passive"))
    )
    (net (code "160") (name "VCC_12V") (class "Default")
      (node (ref "J16") (pin "1") (pinfunction "1_1") (pintype "passive"))
      (node (ref "J17") (pin "1") (pinfunction "1_1") (pintype "passive"))
      (node (ref "J18") (pin "1") (pinfunction "1_1") (pintype "passive"))
      (node (ref "J19") (pin "1") (pinfunction "1_1") (pintype "passive"))
      (node (ref "P1") (pin "1") (pinfunction "1_1") (pintype "passive"))
      (node (ref "P1") (pin "2") (pinfunction "2_2") (pintype "passive"))
      (node (ref "P1") (pin "3") (pinfunction "3_3") (pintype "passive"))
      (node (ref "P1") (pin "4") (pinfunction "4_4") (pintype "passive"))
      (node (ref "TP2") (pin "1") (pinfunction "1_1") (pintype "passive"))
    )
    (net (code "161") (name "unconnected-(IC1-R1IN-Pad13)") (class "Default")
      (node (ref "IC1") (pin "13") (pinfunction "R1IN_13") (pintype "passive+no_connect"))
    )
    (net (code "162") (name "unconnected-(IC1-R1OUT-Pad12)") (class "Default")
      (node (ref "IC1") (pin "12") (pinfunction "R1OUT_12") (pintype "passive+no_connect"))
    )
    (net (code "163") (name "unconnected-(IC1-T1IN-Pad11)") (class "Default")
      (node (ref "IC1") (pin "11") (pinfunction "T1IN_11") (pintype "passive+no_connect"))
    )
    (net (code "164") (name "unconnected-(IC1-T1OUT-Pad14)") (class "Default")
      (node (ref "IC1") (pin "14") (pinfunction "T1OUT_14") (pintype "passive+no_connect"))
    )
    (net (code "165") (name "unconnected-(IC2-RXER{slash}~{PHYAD0}-Pad10)") (class "Default")
      (node (ref "IC2") (pin "10") (pinfunction "RXER/~{PHYAD0}_10") (pintype "passive+no_connect"))
    )
    (net (code "166") (name "unconnected-(IC2-VDDCR-Pad6)") (class "Default")
      (node (ref "IC2") (pin "6") (pinfunction "VDDCR_6") (pintype "passive+no_connect"))
    )
    (net (code "167") (name "unconnected-(J8-Pad1)") (class "Default")
      (node (ref "J8") (pin "1") (pinfunction "1_1") (pintype "passive+no_connect"))
    )
    (net (code "168") (name "unconnected-(J8-Pad4)") (class "Default")
      (node (ref "J8") (pin "4") (pinfunction "4_4") (pintype "passive+no_connect"))
    )
    (net (code "169") (name "unconnected-(J8-Pad6)") (class "Default")
      (node (ref "J8") (pin "6") (pinfunction "6_6") (pintype "passive+no_connect"))
    )
    (net (code "170") (name "unconnected-(J8-Pad7)") (class "Default")
      (node (ref "J8") (pin "7") (pinfunction "7_7") (pintype "passive+no_connect"))
    )
    (net (code "171") (name "unconnected-(J8-Pad8)") (class "Default")
      (node (ref "J8") (pin "8") (pinfunction "8_8") (pintype "passive+no_connect"))
    )
    (net (code "172") (name "unconnected-(J8-Pad9)") (class "Default")
      (node (ref "J8") (pin "9") (pinfunction "9_9") (pintype "passive+no_connect"))
    )
    (net (code "173") (name "unconnected-(M1-AD0-Pad7)") (class "Default")
      (node (ref "M1") (pin "7") (pinfunction "AD0_7") (pintype "passive+no_connect"))
    )
    (net (code "174") (name "unconnected-(M1-INT-Pad8)") (class "Default")
      (node (ref "M1") (pin "8") (pinfunction "INT_8") (pintype "passive+no_connect"))
    )
    (net (code "175") (name "unconnected-(M1-XCL-Pad6)") (class "Default")
      (node (ref "M1") (pin "6") (pinfunction "XCL_6") (pintype "passive+no_connect"))
    )
    (net (code "176") (name "unconnected-(M1-XDA-Pad5)") (class "Default")
      (node (ref "M1") (pin "5") (pinfunction "XDA_5") (pintype "passive+no_connect"))
    )
    (net (code "177") (name "unconnected-(RJ1-PadMH3)") (class "Default")
      (node (ref "RJ1") (pin "MH3") (pinfunction "MH3_MH3") (pintype "passive+no_connect"))
    )
    (net (code "178") (name "unconnected-(RJ1-PadMH4)") (class "Default")
      (node (ref "RJ1") (pin "MH4") (pinfunction "MH4_MH4") (pintype "passive+no_connect"))
    )
    (net (code "179") (name "unconnected-(U2-Vref-Pad5)") (class "Default")
      (node (ref "U2") (pin "5") (pinfunction "Vref_5") (pintype "passive+no_connect"))
    )
    (net (code "180") (name "unconnected-(U3-Vref-Pad5)") (class "Default")
      (node (ref "U3") (pin "5") (pinfunction "Vref_5") (pintype "passive+no_connect"))
    )
  )
)
